# Schaltplan_SMD2.net
KiCad netlist of a schematic drawn in EAGLE
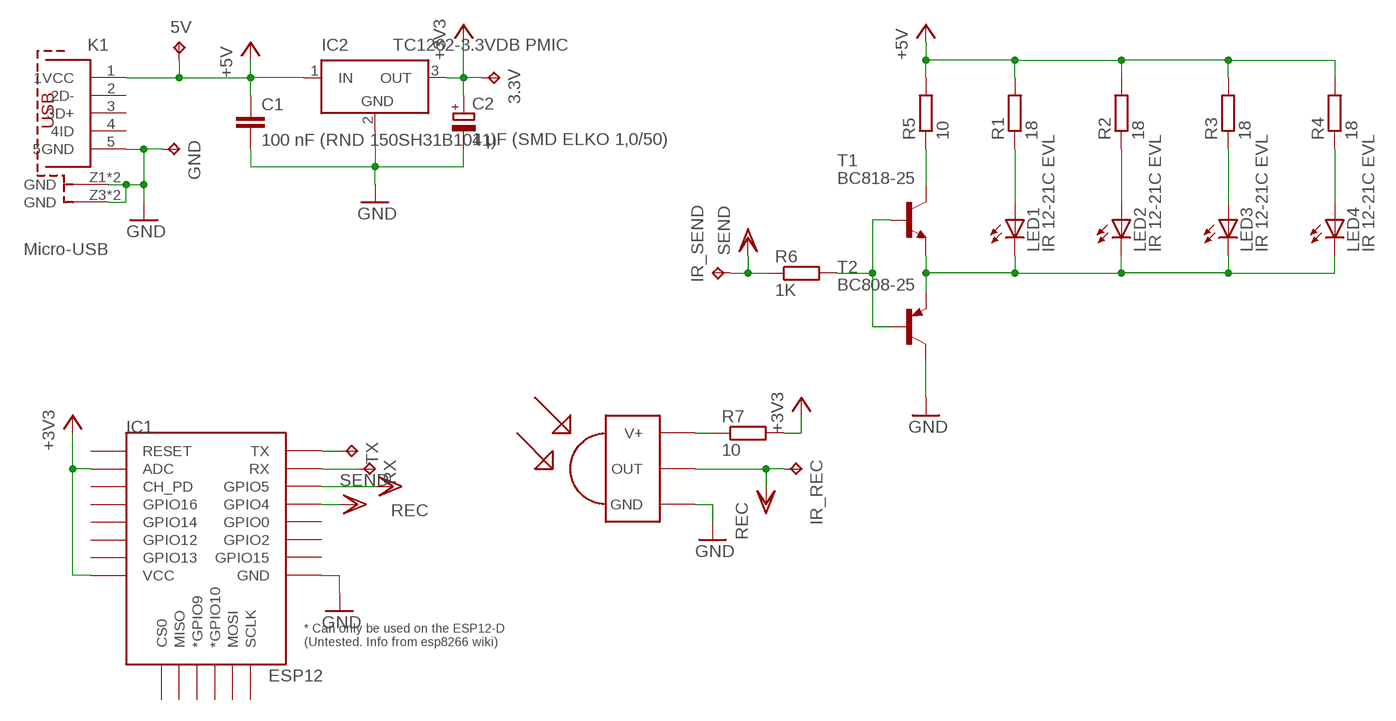
[diagram p0: schematic, sheet 1]

(export (version "E")
  (design (tool "Eeschema 10.0.6"))
  (components
    (comp (ref "3.3V")
      (value "TPB2,54")
      (footprint "eagle-import:B2,54")
      (libsource (lib "eagle-import") (part "TPB2,54"))
    )
    (comp (ref "5V")
      (value "TPB2,54")
      (footprint "eagle-import:B2,54")
      (libsource (lib "eagle-import") (part "TPB2,54"))
    )
    (comp (ref "C1")
      (value "100 nF (RND 150SH31B1041)")
      (footprint "eagle-import:C1206")
      (libsource (lib "eagle-import") (part "C-EUC1206"))
    )
    (comp (ref "C2")
      (value "1 µF (SMD ELKO 1,0/50)")
      (footprint "eagle-import:UD-4X5,8_NICHICON")
      (libsource (lib "eagle-import") (part "CPOL-EUUD-4X5,8"))
    )
    (comp (ref "GND")
      (value "TPB2,54")
      (footprint "eagle-import:B2,54")
      (libsource (lib "eagle-import") (part "TPB2,54"))
    )
    (comp (ref "IC1")
      (value "ESP12")
      (footprint "eagle-import:ESP12E-SMD")
      (libsource (lib "eagle-import") (part "ESP12ESMD"))
    )
    (comp (ref "IC2")
      (value "TC1262-3.3VDB PMIC")
      (footprint "eagle-import:SOT223")
      (fields (field (name "MPN") "LT1129CST-5#PBF"))
      (libsource (lib "eagle-import") (part "LT1129CST5"))
    )
    (comp (ref "IR-TRANSMITTER")
      (value "TSOP1833")
      (footprint "eagle-import:TSOP18XX")
      (libsource (lib "eagle-import") (part "TSOP1833"))
    )
    (comp (ref "IR_REC")
      (value "TPB2,54")
      (footprint "eagle-import:B2,54")
      (libsource (lib "eagle-import") (part "TPB2,54"))
    )
    (comp (ref "IR_SEND")
      (value "TPB2,54")
      (footprint "eagle-import:B2,54")
      (libsource (lib "eagle-import") (part "TPB2,54"))
    )
    (comp (ref "K1")
      (value "Micro-USB")
      (footprint "eagle-import:629105150521")
      (libsource (lib "eagle-import") (part "629105150521"))
    )
    (comp (ref "LED1")
      (value "IR 12-21C EVL")
      (footprint "eagle-import:CHIPLED_1206")
      (libsource (lib "eagle-import") (part "LEDCHIPLED_1206"))
    )
    (comp (ref "LED2")
      (value "IR 12-21C EVL")
      (footprint "eagle-import:CHIPLED_1206")
      (libsource (lib "eagle-import") (part "LEDCHIPLED_1206"))
    )
    (comp (ref "LED3")
      (value "IR 12-21C EVL")
      (footprint "eagle-import:CHIPLED_1206")
      (libsource (lib "eagle-import") (part "LEDCHIPLED_1206"))
    )
    (comp (ref "LED4")
      (value "IR 12-21C EVL")
      (footprint "eagle-import:CHIPLED_1206")
      (libsource (lib "eagle-import") (part "LEDCHIPLED_1206"))
    )
    (comp (ref "R1")
      (value "18")
      (footprint "eagle-import:R1206W")
      (libsource (lib "eagle-import") (part "R-EU_R1206W"))
    )
    (comp (ref "R2")
      (value "18")
      (footprint "eagle-import:R1206W")
      (libsource (lib "eagle-import") (part "R-EU_R1206W"))
    )
    (comp (ref "R3")
      (value "18")
      (footprint "eagle-import:R1206W")
      (libsource (lib "eagle-import") (part "R-EU_R1206W"))
    )
    (comp (ref "R4")
      (value "18")
      (footprint "eagle-import:R1206W")
      (libsource (lib "eagle-import") (part "R-EU_R1206W"))
    )
    (comp (ref "R5")
      (value "10")
      (footprint "eagle-import:R1206W")
      (libsource (lib "eagle-import") (part "R-EU_R1206W"))
    )
    (comp (ref "R6")
      (value "1K")
      (footprint "eagle-import:R1206W")
      (libsource (lib "eagle-import") (part "R-EU_R1206W"))
    )
    (comp (ref "R7")
      (value "10")
      (footprint "eagle-import:R1206W")
      (libsource (lib "eagle-import") (part "R-EU_R1206W"))
    )
    (comp (ref "RX")
      (value "TPB2,54")
      (footprint "eagle-import:B2,54")
      (libsource (lib "eagle-import") (part "TPB2,54"))
    )
    (comp (ref "T1")
      (value "BC818-25")
      (footprint "eagle-import:SOT23-BEC")
      (libsource (lib "eagle-import") (part "BC818SMD-25"))
    )
    (comp (ref "T2")
      (value "BC808-25")
      (footprint "eagle-import:SOT23-BEC")
      (libsource (lib "eagle-import") (part "BC808SMD-25"))
    )
    (comp (ref "TX")
      (value "TPB2,54")
      (footprint "eagle-import:B2,54")
      (libsource (lib "eagle-import") (part "TPB2,54"))
    )
  )
  (nets
    (net (code "1") (name "+3V3") (class "Default")
      (node (ref "3.3V") (pin "TP") (pinfunction "TP_TP") (pintype "input"))
      (node (ref "C2") (pin "+") (pinfunction "+_+") (pintype "passive"))
      (node (ref "IC1") (pin "ADC") (pinfunction "ADC_ADC") (pintype "bidirectional"))
      (node (ref "IC1") (pin "VCC") (pinfunction "VCC_VCC") (pintype "bidirectional"))
      (node (ref "IC2") (pin "3") (pinfunction "OUT_3") (pintype "output"))
      (node (ref "R7") (pin "2") (pinfunction "2_2") (pintype "passive"))
    )
    (net (code "2") (name "+5V") (class "Default")
      (node (ref "5V") (pin "TP") (pinfunction "TP_TP") (pintype "input"))
      (node (ref "C1") (pin "1") (pinfunction "1_1") (pintype "passive"))
      (node (ref "IC2") (pin "1") (pinfunction "IN_1") (pintype "input"))
      (node (ref "K1") (pin "1") (pinfunction "1VCC_1") (pintype "passive"))
      (node (ref "R1") (pin "2") (pinfunction "2_2") (pintype "passive"))
      (node (ref "R2") (pin "2") (pinfunction "2_2") (pintype "passive"))
      (node (ref "R3") (pin "2") (pinfunction "2_2") (pintype "passive"))
      (node (ref "R4") (pin "2") (pinfunction "2_2") (pintype "passive"))
      (node (ref "R5") (pin "2") (pinfunction "2_2") (pintype "passive"))
    )
    (net (code "3") (name "GND") (class "Default")
      (node (ref "C1") (pin "2") (pinfunction "2_2") (pintype "passive"))
      (node (ref "C2") (pin "-") (pinfunction "-_-") (pintype "passive"))
      (node (ref "GND") (pin "TP") (pinfunction "TP_TP") (pintype "input"))
      (node (ref "IC1") (pin "GND") (pinfunction "GND_GND") (pintype "bidirectional"))
      (node (ref "IC2") (pin "2") (pinfunction "GND_2") (pintype "power_in"))
      (node (ref "IR-TRANSMITTER") (pin "GND") (pinfunction "GND_GND") (pintype "bidirectional"))
      (node (ref "K1") (pin "5") (pinfunction "5GND_5") (pintype "passive"))
      (node (ref "K1") (pin "Z1") (pinfunction "GND_Z1") (pintype "bidirectional"))
      (node (ref "K1") (pin "Z2") (pinfunction "GND_Z2") (pintype "bidirectional"))
      (node (ref "K1") (pin "Z3") (pinfunction "GND_Z3") (pintype "bidirectional"))
      (node (ref "K1") (pin "Z4") (pinfunction "GND_Z4") (pintype "bidirectional"))
      (node (ref "T2") (pin "C") (pinfunction "C_C") (pintype "passive"))
    )
    (net (code "4") (name "Net-(IC1-RX)") (class "Default")
      (node (ref "IC1") (pin "RXD0") (pinfunction "RX_RXD0") (pintype "bidirectional"))
      (node (ref "RX") (pin "TP") (pinfunction "TP_TP") (pintype "input"))
    )
    (net (code "5") (name "Net-(IC1-TX)") (class "Default")
      (node (ref "IC1") (pin "TXD0") (pinfunction "TX_TXD0") (pintype "bidirectional"))
      (node (ref "TX") (pin "TP") (pinfunction "TP_TP") (pintype "input"))
    )
    (net (code "6") (name "Net-(IR-TRANSMITTER-V+)") (class "Default")
      (node (ref "IR-TRANSMITTER") (pin "VCC") (pinfunction "V+_VCC") (pintype "bidirectional"))
      (node (ref "R7") (pin "1") (pinfunction "1_1") (pintype "passive"))
    )
    (net (code "7") (name "Net-(LED1-PadA)") (class "Default")
      (node (ref "LED1") (pin "A") (pinfunction "A_A") (pintype "passive"))
      (node (ref "R1") (pin "1") (pinfunction "1_1") (pintype "passive"))
    )
    (net (code "8") (name "Net-(LED1-PadC)") (class "Default")
      (node (ref "LED1") (pin "C") (pinfunction "C_C") (pintype "passive"))
      (node (ref "LED2") (pin "C") (pinfunction "C_C") (pintype "passive"))
      (node (ref "LED3") (pin "C") (pinfunction "C_C") (pintype "passive"))
      (node (ref "LED4") (pin "C") (pinfunction "C_C") (pintype "passive"))
      (node (ref "T1") (pin "E") (pinfunction "E_E") (pintype "passive"))
      (node (ref "T2") (pin "E") (pinfunction "E_E") (pintype "passive"))
    )
    (net (code "9") (name "Net-(LED2-PadA)") (class "Default")
      (node (ref "LED2") (pin "A") (pinfunction "A_A") (pintype "passive"))
      (node (ref "R2") (pin "1") (pinfunction "1_1") (pintype "passive"))
    )
    (net (code "10") (name "Net-(LED3-PadA)") (class "Default")
      (node (ref "LED3") (pin "A") (pinfunction "A_A") (pintype "passive"))
      (node (ref "R3") (pin "1") (pinfunction "1_1") (pintype "passive"))
    )
    (net (code "11") (name "Net-(LED4-PadA)") (class "Default")
      (node (ref "LED4") (pin "A") (pinfunction "A_A") (pintype "passive"))
      (node (ref "R4") (pin "1") (pinfunction "1_1") (pintype "passive"))
    )
    (net (code "12") (name "Net-(R5-Pad1)") (class "Default")
      (node (ref "R5") (pin "1") (pinfunction "1_1") (pintype "passive"))
      (node (ref "T1") (pin "C") (pinfunction "C_C") (pintype "passive"))
    )
    (net (code "13") (name "Net-(R6-Pad2)") (class "Default")
      (node (ref "R6") (pin "2") (pinfunction "2_2") (pintype "passive"))
      (node (ref "T1") (pin "B") (pinfunction "B_B") (pintype "passive"))
      (node (ref "T2") (pin "B") (pinfunction "B_B") (pintype "passive"))
    )
    (net (code "14") (name "REC") (class "Default")
      (node (ref "IC1") (pin "GPIO5") (pinfunction "GPIO5_GPIO5") (pintype "bidirectional"))
      (node (ref "IR-TRANSMITTER") (pin "OUT") (pinfunction "OUT_OUT") (pintype "bidirectional"))
      (node (ref "IR_REC") (pin "TP") (pinfunction "TP_TP") (pintype "input"))
    )
    (net (code "15") (name "SEND") (class "Default")
      (node (ref "IC1") (pin "GPIO4") (pinfunction "GPIO4_GPIO4") (pintype "bidirectional"))
      (node (ref "IR_SEND") (pin "TP") (pinfunction "TP_TP") (pintype "input"))
      (node (ref "R6") (pin "1") (pinfunction "1_1") (pintype "passive"))
    )
    (net (code "16") (name "unconnected-(IC1-*GPIO9-PadGPIO9)") (class "Default")
      (node (ref "IC1") (pin "GPIO9") (pinfunction "*GPIO9_GPIO9") (pintype "bidirectional"))
    )
    (net (code "17") (name "unconnected-(IC1-*GPIO10-PadGPIO10)") (class "Default")
      (node (ref "IC1") (pin "GPIO10") (pinfunction "*GPIO10_GPIO10") (pintype "bidirectional"))
    )
    (net (code "18") (name "unconnected-(IC1-PadCH_PD)") (class "Default")
      (node (ref "IC1") (pin "CH_PD") (pinfunction "CH_PD_CH_PD") (pintype "bidirectional"))
    )
    (net (code "19") (name "unconnected-(IC1-PadCS0)") (class "Default")
      (node (ref "IC1") (pin "CS0") (pinfunction "CS0_CS0") (pintype "bidirectional"))
    )
    (net (code "20") (name "unconnected-(IC1-PadGPIO0)") (class "Default")
      (node (ref "IC1") (pin "GPIO0") (pinfunction "GPIO0_GPIO0") (pintype "bidirectional"))
    )
    (net (code "21") (name "unconnected-(IC1-PadGPIO2)") (class "Default")
      (node (ref "IC1") (pin "GPIO2") (pinfunction "GPIO2_GPIO2") (pintype "bidirectional"))
    )
    (net (code "22") (name "unconnected-(IC1-PadGPIO12)") (class "Default")
      (node (ref "IC1") (pin "GPIO12") (pinfunction "GPIO12_GPIO12") (pintype "bidirectional"))
    )
    (net (code "23") (name "unconnected-(IC1-PadGPIO13)") (class "Default")
      (node (ref "IC1") (pin "GPIO13") (pinfunction "GPIO13_GPIO13") (pintype "bidirectional"))
    )
    (net (code "24") (name "unconnected-(IC1-PadGPIO14)") (class "Default")
      (node (ref "IC1") (pin "GPIO14") (pinfunction "GPIO14_GPIO14") (pintype "bidirectional"))
    )
    (net (code "25") (name "unconnected-(IC1-PadGPIO15)") (class "Default")
      (node (ref "IC1") (pin "GPIO15") (pinfunction "GPIO15_GPIO15") (pintype "bidirectional"))
    )
    (net (code "26") (name "unconnected-(IC1-PadGPIO16)") (class "Default")
      (node (ref "IC1") (pin "GPIO16") (pinfunction "GPIO16_GPIO16") (pintype "bidirectional"))
    )
    (net (code "27") (name "unconnected-(IC1-PadMISO)") (class "Default")
      (node (ref "IC1") (pin "MISO") (pinfunction "MISO_MISO") (pintype "bidirectional"))
    )
    (net (code "28") (name "unconnected-(IC1-PadMOSI)") (class "Default")
      (node (ref "IC1") (pin "MOSI") (pinfunction "MOSI_MOSI") (pintype "bidirectional"))
    )
    (net (code "29") (name "unconnected-(IC1-PadRESET)") (class "Default")
      (node (ref "IC1") (pin "RESET") (pinfunction "RESET_RESET") (pintype "bidirectional"))
    )
    (net (code "30") (name "unconnected-(IC1-PadSCLK)") (class "Default")
      (node (ref "IC1") (pin "SCLK") (pinfunction "SCLK_SCLK") (pintype "bidirectional"))
    )
    (net (code "31") (name "unconnected-(K1-2D--Pad2)") (class "Default")
      (node (ref "K1") (pin "2") (pinfunction "2D-_2") (pintype "passive"))
    )
    (net (code "32") (name "unconnected-(K1-3D+-Pad3)") (class "Default")
      (node (ref "K1") (pin "3") (pinfunction "3D+_3") (pintype "passive"))
    )
    (net (code "33") (name "unconnected-(K1-4ID-Pad4)") (class "Default")
      (node (ref "K1") (pin "4") (pinfunction "4ID_4") (pintype "passive"))
    )
  )
)
